# output_module.net
KiCad netlist of a schematic drawn in Altium Designer
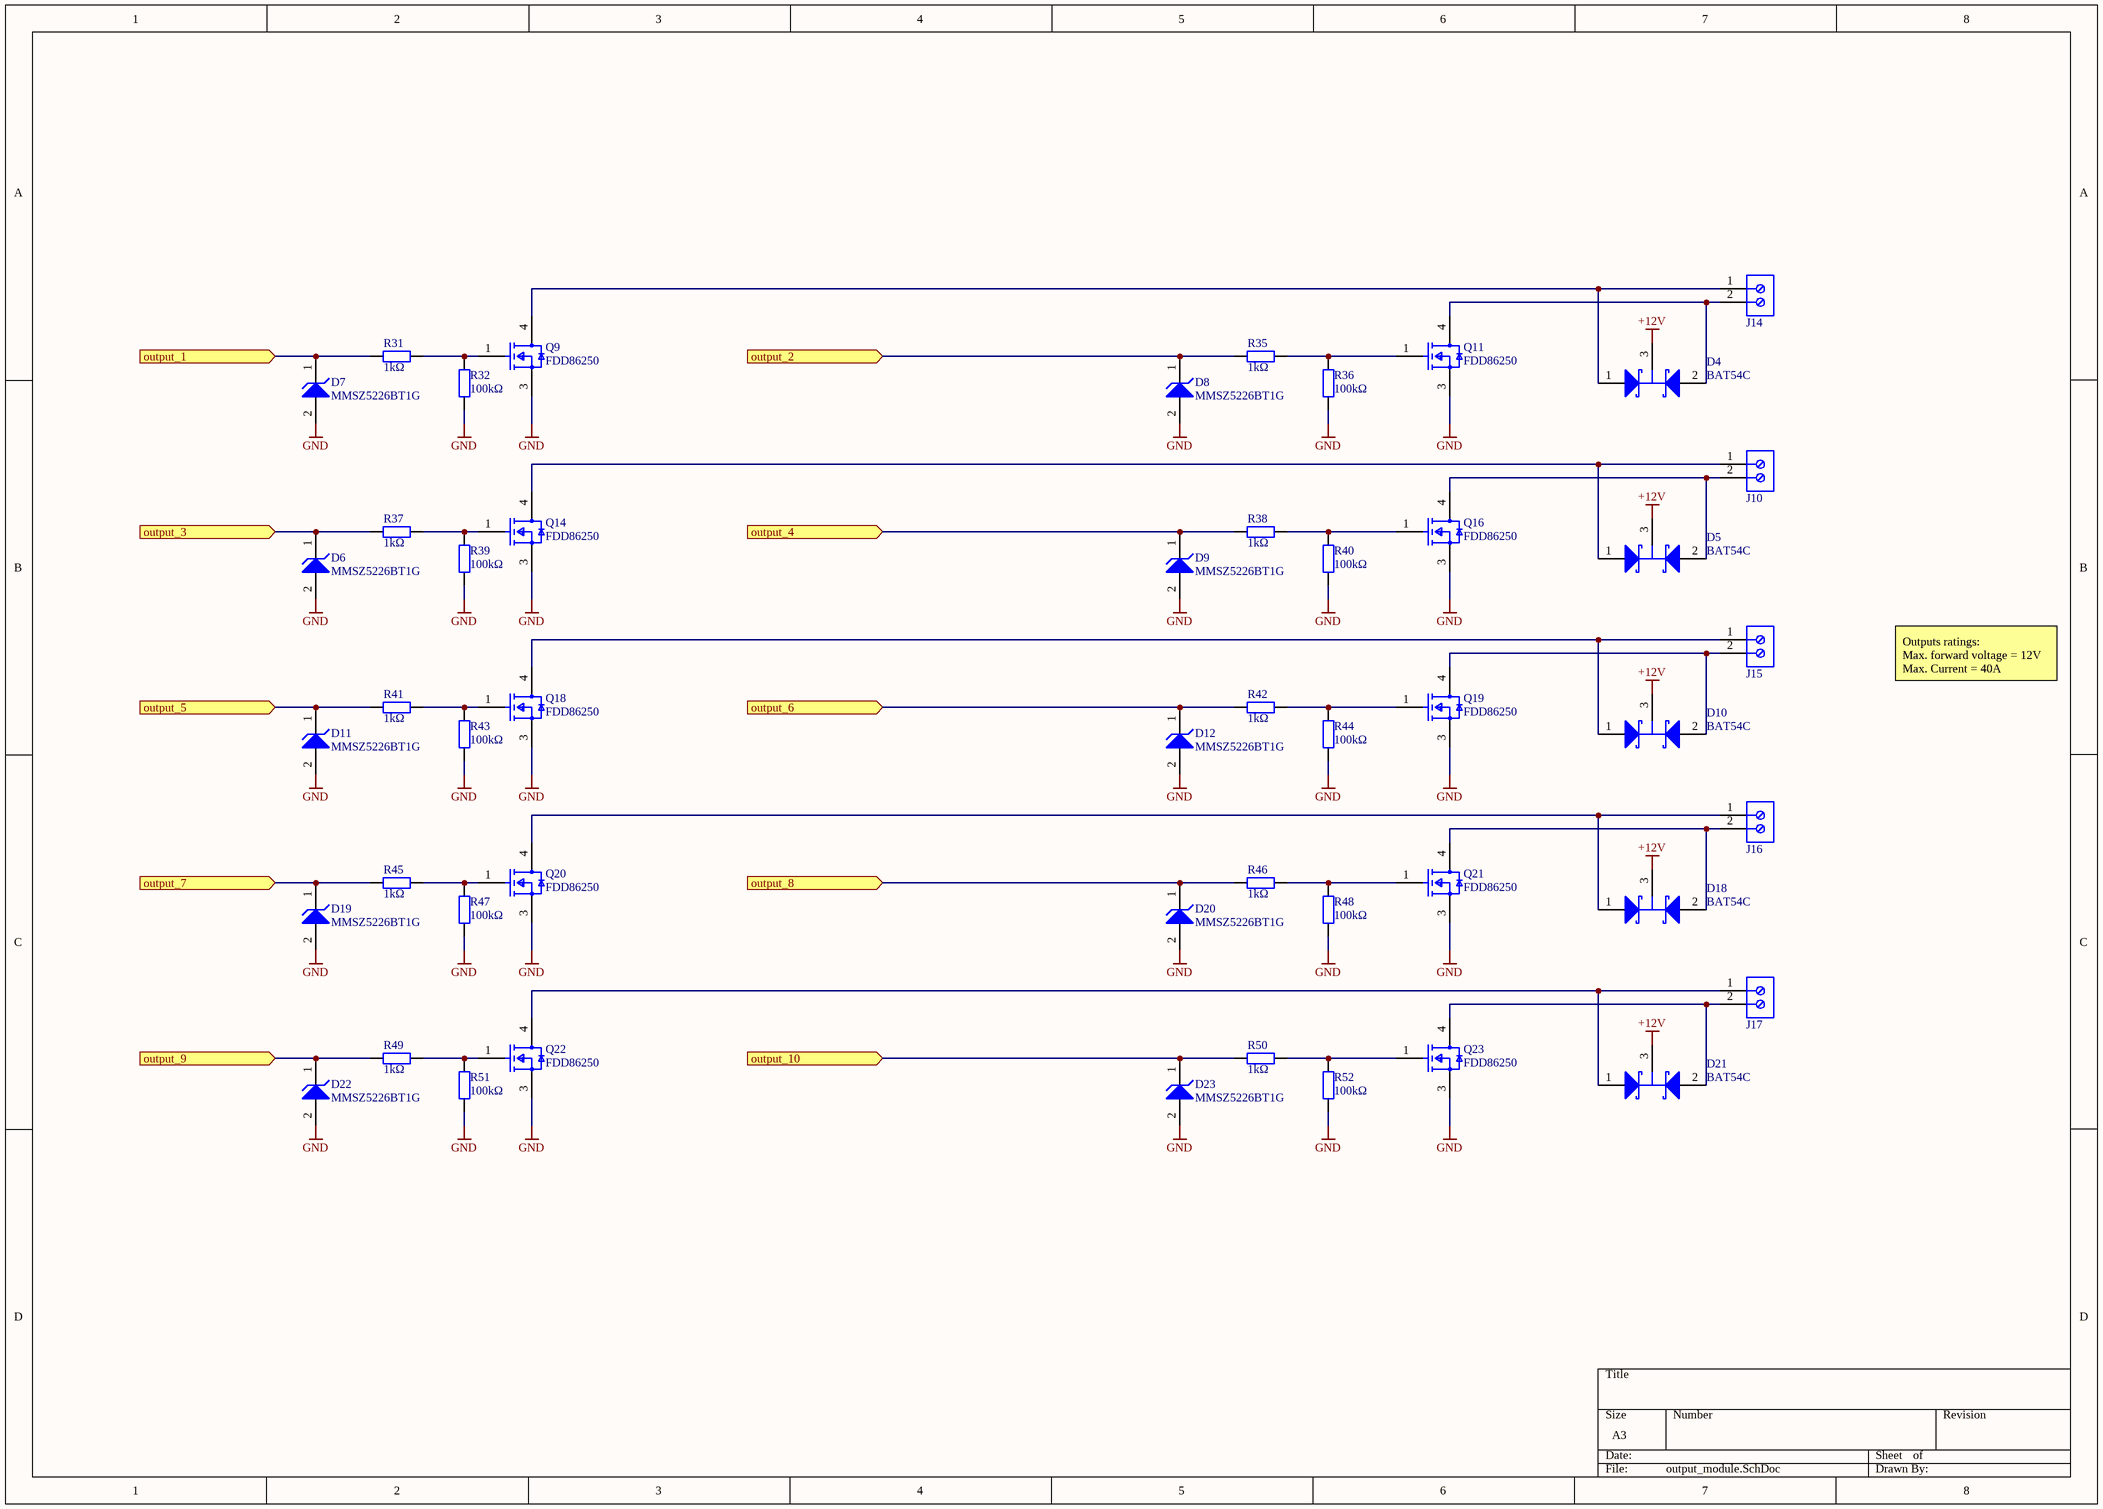
[diagram p0: output_module.SchDoc]

(export (version "E")
  (design (tool "Eeschema 10.0.6"))
  (components
    (comp (ref "D4")
      (value "BAT54C")
      (footprint "SOT-23")
      (description "Schottky Barrier Diode, 30 V, 3-Pin SOT23, RoHS, Tape and Reel")
      (fields (field (name "MANUFACTURER") "NXP Semiconductors"))
      (libsource (lib "integrated_library") (part "DIODE_BAT54C"))
    )
    (comp (ref "D5")
      (value "BAT54C")
      (footprint "SOT-23")
      (description "Schottky Barrier Diode, 30 V, 3-Pin SOT23, RoHS, Tape and Reel")
      (fields (field (name "MANUFACTURER") "NXP Semiconductors"))
      (libsource (lib "integrated_library") (part "DIODE_BAT54C"))
    )
    (comp (ref "D6")
      (value "MMSZ5226BT1G")
      (footprint "ONSC-SOD-123-2-425-04_V")
      (description "Zener Voltage Regulator, 500 mW, 2-Pin SOD-123, Pb-Free, Tape and Reel")
      (fields (field (name "MANUFACTURER") "On Semiconductor"))
      (libsource (lib "Altium Content Vault") (part "ONSC-K1A2-2"))
    )
    (comp (ref "D7")
      (value "MMSZ5226BT1G")
      (footprint "ONSC-SOD-123-2-425-04_V")
      (description "Zener Voltage Regulator, 500 mW, 2-Pin SOD-123, Pb-Free, Tape and Reel")
      (fields (field (name "MANUFACTURER") "On Semiconductor"))
      (libsource (lib "Altium Content Vault") (part "ONSC-K1A2-2"))
    )
    (comp (ref "D8")
      (value "MMSZ5226BT1G")
      (footprint "ONSC-SOD-123-2-425-04_V")
      (description "Zener Voltage Regulator, 500 mW, 2-Pin SOD-123, Pb-Free, Tape and Reel")
      (fields (field (name "MANUFACTURER") "On Semiconductor"))
      (libsource (lib "Altium Content Vault") (part "ONSC-K1A2-2"))
    )
    (comp (ref "D9")
      (value "MMSZ5226BT1G")
      (footprint "ONSC-SOD-123-2-425-04_V")
      (description "Zener Voltage Regulator, 500 mW, 2-Pin SOD-123, Pb-Free, Tape and Reel")
      (fields (field (name "MANUFACTURER") "On Semiconductor"))
      (libsource (lib "Altium Content Vault") (part "ONSC-K1A2-2"))
    )
    (comp (ref "D10")
      (value "BAT54C")
      (footprint "SOT-23")
      (description "Schottky Barrier Diode, 30 V, 3-Pin SOT23, RoHS, Tape and Reel")
      (fields (field (name "MANUFACTURER") "NXP Semiconductors"))
      (libsource (lib "integrated_library") (part "DIODE_BAT54C"))
    )
    (comp (ref "D11")
      (value "MMSZ5226BT1G")
      (footprint "ONSC-SOD-123-2-425-04_V")
      (description "Zener Voltage Regulator, 500 mW, 2-Pin SOD-123, Pb-Free, Tape and Reel")
      (fields (field (name "MANUFACTURER") "On Semiconductor"))
      (libsource (lib "Altium Content Vault") (part "ONSC-K1A2-2"))
    )
    (comp (ref "D12")
      (value "MMSZ5226BT1G")
      (footprint "ONSC-SOD-123-2-425-04_V")
      (description "Zener Voltage Regulator, 500 mW, 2-Pin SOD-123, Pb-Free, Tape and Reel")
      (fields (field (name "MANUFACTURER") "On Semiconductor"))
      (libsource (lib "Altium Content Vault") (part "ONSC-K1A2-2"))
    )
    (comp (ref "D18")
      (value "BAT54C")
      (footprint "SOT-23")
      (description "Schottky Barrier Diode, 30 V, 3-Pin SOT23, RoHS, Tape and Reel")
      (fields (field (name "MANUFACTURER") "NXP Semiconductors"))
      (libsource (lib "integrated_library") (part "DIODE_BAT54C"))
    )
    (comp (ref "D19")
      (value "MMSZ5226BT1G")
      (footprint "ONSC-SOD-123-2-425-04_V")
      (description "Zener Voltage Regulator, 500 mW, 2-Pin SOD-123, Pb-Free, Tape and Reel")
      (fields (field (name "MANUFACTURER") "On Semiconductor"))
      (libsource (lib "Altium Content Vault") (part "ONSC-K1A2-2"))
    )
    (comp (ref "D20")
      (value "MMSZ5226BT1G")
      (footprint "ONSC-SOD-123-2-425-04_V")
      (description "Zener Voltage Regulator, 500 mW, 2-Pin SOD-123, Pb-Free, Tape and Reel")
      (fields (field (name "MANUFACTURER") "On Semiconductor"))
      (libsource (lib "Altium Content Vault") (part "ONSC-K1A2-2"))
    )
    (comp (ref "D21")
      (value "BAT54C")
      (footprint "SOT-23")
      (description "Schottky Barrier Diode, 30 V, 3-Pin SOT23, RoHS, Tape and Reel")
      (fields (field (name "MANUFACTURER") "NXP Semiconductors"))
      (libsource (lib "integrated_library") (part "DIODE_BAT54C"))
    )
    (comp (ref "D22")
      (value "MMSZ5226BT1G")
      (footprint "ONSC-SOD-123-2-425-04_V")
      (description "Zener Voltage Regulator, 500 mW, 2-Pin SOD-123, Pb-Free, Tape and Reel")
      (fields (field (name "MANUFACTURER") "On Semiconductor"))
      (libsource (lib "Altium Content Vault") (part "ONSC-K1A2-2"))
    )
    (comp (ref "D23")
      (value "MMSZ5226BT1G")
      (footprint "ONSC-SOD-123-2-425-04_V")
      (description "Zener Voltage Regulator, 500 mW, 2-Pin SOD-123, Pb-Free, Tape and Reel")
      (fields (field (name "MANUFACTURER") "On Semiconductor"))
      (libsource (lib "Altium Content Vault") (part "ONSC-K1A2-2"))
    )
    (comp (ref "J10")
      (value "282836-2")
      (footprint "TECO-282836-2_V")
      (description "Female Header, Pitch 5 mm, 1 x 2 Position, Height 10 mm, Tail Length 3.5 mm, Rohs, Bulk")
      (fields (field (name "VOLTAGE") "300V") (field (name "MANUFACTURER") "TE Connectivity"))
      (libsource (lib "Altium Content Vault") (part "CN-1P-F-TB2"))
    )
    (comp (ref "J14")
      (value "282836-2")
      (footprint "TECO-282836-2_V")
      (description "Female Header, Pitch 5 mm, 1 x 2 Position, Height 10 mm, Tail Length 3.5 mm, Rohs, Bulk")
      (fields (field (name "VOLTAGE") "300V") (field (name "MANUFACTURER") "TE Connectivity"))
      (libsource (lib "Altium Content Vault") (part "CN-1P-F-TB2"))
    )
    (comp (ref "J15")
      (value "282836-2")
      (footprint "TECO-282836-2_V")
      (description "Female Header, Pitch 5 mm, 1 x 2 Position, Height 10 mm, Tail Length 3.5 mm, Rohs, Bulk")
      (fields (field (name "VOLTAGE") "300V") (field (name "MANUFACTURER") "TE Connectivity"))
      (libsource (lib "Altium Content Vault") (part "CN-1P-F-TB2"))
    )
    (comp (ref "J16")
      (value "282836-2")
      (footprint "TECO-282836-2_V")
      (description "Female Header, Pitch 5 mm, 1 x 2 Position, Height 10 mm, Tail Length 3.5 mm, Rohs, Bulk")
      (fields (field (name "VOLTAGE") "300V") (field (name "MANUFACTURER") "TE Connectivity"))
      (libsource (lib "Altium Content Vault") (part "CN-1P-F-TB2"))
    )
    (comp (ref "J17")
      (value "282836-2")
      (footprint "TECO-282836-2_V")
      (description "Female Header, Pitch 5 mm, 1 x 2 Position, Height 10 mm, Tail Length 3.5 mm, Rohs, Bulk")
      (fields (field (name "VOLTAGE") "300V") (field (name "MANUFACTURER") "TE Connectivity"))
      (libsource (lib "Altium Content Vault") (part "CN-1P-F-TB2"))
    )
    (comp (ref "Q9")
      (value "FDD86250")
      (footprint "FP-369AS-MFG")
      (description "MOSFET N-CH 150V 8A DPAK")
      (fields
        (field (name "MANUFACTURER") "ON Semiconductor")
        (field (name "OCTOPART") "https://octopart.com/fdd86250-on+semiconductor-84325855")
      )
      (libsource (lib "Altium Content Vault") (part "7ccf16d7e298eaa7d64fcf34af6bb8b"))
    )
    (comp (ref "Q11")
      (value "FDD86250")
      (footprint "FP-369AS-MFG")
      (description "MOSFET N-CH 150V 8A DPAK")
      (fields
        (field (name "MANUFACTURER") "ON Semiconductor")
        (field (name "OCTOPART") "https://octopart.com/fdd86250-on+semiconductor-84325855")
      )
      (libsource (lib "Altium Content Vault") (part "7ccf16d7e298eaa7d64fcf34af6bb8b"))
    )
    (comp (ref "Q14")
      (value "FDD86250")
      (footprint "FP-369AS-MFG")
      (description "MOSFET N-CH 150V 8A DPAK")
      (fields
        (field (name "MANUFACTURER") "ON Semiconductor")
        (field (name "OCTOPART") "https://octopart.com/fdd86250-on+semiconductor-84325855")
      )
      (libsource (lib "Altium Content Vault") (part "7ccf16d7e298eaa7d64fcf34af6bb8b"))
    )
    (comp (ref "Q16")
      (value "FDD86250")
      (footprint "FP-369AS-MFG")
      (description "MOSFET N-CH 150V 8A DPAK")
      (fields
        (field (name "MANUFACTURER") "ON Semiconductor")
        (field (name "OCTOPART") "https://octopart.com/fdd86250-on+semiconductor-84325855")
      )
      (libsource (lib "Altium Content Vault") (part "7ccf16d7e298eaa7d64fcf34af6bb8b"))
    )
    (comp (ref "Q18")
      (value "FDD86250")
      (footprint "FP-369AS-MFG")
      (description "MOSFET N-CH 150V 8A DPAK")
      (fields
        (field (name "MANUFACTURER") "ON Semiconductor")
        (field (name "OCTOPART") "https://octopart.com/fdd86250-on+semiconductor-84325855")
      )
      (libsource (lib "Altium Content Vault") (part "7ccf16d7e298eaa7d64fcf34af6bb8b"))
    )
    (comp (ref "Q19")
      (value "FDD86250")
      (footprint "FP-369AS-MFG")
      (description "MOSFET N-CH 150V 8A DPAK")
      (fields
        (field (name "MANUFACTURER") "ON Semiconductor")
        (field (name "OCTOPART") "https://octopart.com/fdd86250-on+semiconductor-84325855")
      )
      (libsource (lib "Altium Content Vault") (part "7ccf16d7e298eaa7d64fcf34af6bb8b"))
    )
    (comp (ref "Q20")
      (value "FDD86250")
      (footprint "FP-369AS-MFG")
      (description "MOSFET N-CH 150V 8A DPAK")
      (fields
        (field (name "MANUFACTURER") "ON Semiconductor")
        (field (name "OCTOPART") "https://octopart.com/fdd86250-on+semiconductor-84325855")
      )
      (libsource (lib "Altium Content Vault") (part "7ccf16d7e298eaa7d64fcf34af6bb8b"))
    )
    (comp (ref "Q21")
      (value "FDD86250")
      (footprint "FP-369AS-MFG")
      (description "MOSFET N-CH 150V 8A DPAK")
      (fields
        (field (name "MANUFACTURER") "ON Semiconductor")
        (field (name "OCTOPART") "https://octopart.com/fdd86250-on+semiconductor-84325855")
      )
      (libsource (lib "Altium Content Vault") (part "7ccf16d7e298eaa7d64fcf34af6bb8b"))
    )
    (comp (ref "Q22")
      (value "FDD86250")
      (footprint "FP-369AS-MFG")
      (description "MOSFET N-CH 150V 8A DPAK")
      (fields
        (field (name "MANUFACTURER") "ON Semiconductor")
        (field (name "OCTOPART") "https://octopart.com/fdd86250-on+semiconductor-84325855")
      )
      (libsource (lib "Altium Content Vault") (part "7ccf16d7e298eaa7d64fcf34af6bb8b"))
    )
    (comp (ref "Q23")
      (value "FDD86250")
      (footprint "FP-369AS-MFG")
      (description "MOSFET N-CH 150V 8A DPAK")
      (fields
        (field (name "MANUFACTURER") "ON Semiconductor")
        (field (name "OCTOPART") "https://octopart.com/fdd86250-on+semiconductor-84325855")
      )
      (libsource (lib "Altium Content Vault") (part "7ccf16d7e298eaa7d64fcf34af6bb8b"))
    )
    (comp (ref "R31")
      (value "1kΩ")
      (footprint "RESC2013X50X30ML20T20")
      (description "Resistor")
      (libsource (lib "PCB_Project") (part "Res_0805"))
    )
    (comp (ref "R32")
      (value "100kΩ")
      (footprint "RESC2013X50X30ML20T20")
      (description "Resistor")
      (libsource (lib "") (part "Res_0805_1"))
    )
    (comp (ref "R35")
      (value "1kΩ")
      (footprint "RESC2013X50X30ML20T20")
      (description "Resistor")
      (libsource (lib "PCB_Project") (part "Res_0805"))
    )
    (comp (ref "R36")
      (value "100kΩ")
      (footprint "RESC2013X50X30ML20T20")
      (description "Resistor")
      (libsource (lib "") (part "Res_0805_1"))
    )
    (comp (ref "R37")
      (value "1kΩ")
      (footprint "RESC2013X50X30ML20T20")
      (description "Resistor")
      (libsource (lib "PCB_Project") (part "Res_0805"))
    )
    (comp (ref "R38")
      (value "1kΩ")
      (footprint "RESC2013X50X30ML20T20")
      (description "Resistor")
      (libsource (lib "PCB_Project") (part "Res_0805"))
    )
    (comp (ref "R39")
      (value "100kΩ")
      (footprint "RESC2013X50X30ML20T20")
      (description "Resistor")
      (libsource (lib "") (part "Res_0805_1"))
    )
    (comp (ref "R40")
      (value "100kΩ")
      (footprint "RESC2013X50X30ML20T20")
      (description "Resistor")
      (libsource (lib "") (part "Res_0805_1"))
    )
    (comp (ref "R41")
      (value "1kΩ")
      (footprint "RESC2013X50X30ML20T20")
      (description "Resistor")
      (libsource (lib "PCB_Project") (part "Res_0805"))
    )
    (comp (ref "R42")
      (value "1kΩ")
      (footprint "RESC2013X50X30ML20T20")
      (description "Resistor")
      (libsource (lib "PCB_Project") (part "Res_0805"))
    )
    (comp (ref "R43")
      (value "100kΩ")
      (footprint "RESC2013X50X30ML20T20")
      (description "Resistor")
      (libsource (lib "") (part "Res_0805_1"))
    )
    (comp (ref "R44")
      (value "100kΩ")
      (footprint "RESC2013X50X30ML20T20")
      (description "Resistor")
      (libsource (lib "") (part "Res_0805_1"))
    )
    (comp (ref "R45")
      (value "1kΩ")
      (footprint "RESC2013X50X30ML20T20")
      (description "Resistor")
      (libsource (lib "PCB_Project") (part "Res_0805"))
    )
    (comp (ref "R46")
      (value "1kΩ")
      (footprint "RESC2013X50X30ML20T20")
      (description "Resistor")
      (libsource (lib "PCB_Project") (part "Res_0805"))
    )
    (comp (ref "R47")
      (value "100kΩ")
      (footprint "RESC2013X50X30ML20T20")
      (description "Resistor")
      (libsource (lib "") (part "Res_0805_1"))
    )
    (comp (ref "R48")
      (value "100kΩ")
      (footprint "RESC2013X50X30ML20T20")
      (description "Resistor")
      (libsource (lib "") (part "Res_0805_1"))
    )
    (comp (ref "R49")
      (value "1kΩ")
      (footprint "RESC2013X50X30ML20T20")
      (description "Resistor")
      (libsource (lib "PCB_Project") (part "Res_0805"))
    )
    (comp (ref "R50")
      (value "1kΩ")
      (footprint "RESC2013X50X30ML20T20")
      (description "Resistor")
      (libsource (lib "PCB_Project") (part "Res_0805"))
    )
    (comp (ref "R51")
      (value "100kΩ")
      (footprint "RESC2013X50X30ML20T20")
      (description "Resistor")
      (libsource (lib "") (part "Res_0805_1"))
    )
    (comp (ref "R52")
      (value "100kΩ")
      (footprint "RESC2013X50X30ML20T20")
      (description "Resistor")
      (libsource (lib "") (part "Res_0805_1"))
    )
  )
  (nets
    (net (code "1") (name "+12V") (class "Default")
      (node (ref "D10") (pin "3") (pinfunction "K_3") (pintype "passive"))
      (node (ref "D18") (pin "3") (pinfunction "K_3") (pintype "passive"))
      (node (ref "D21") (pin "3") (pinfunction "K_3") (pintype "passive"))
      (node (ref "D4") (pin "3") (pinfunction "K_3") (pintype "passive"))
      (node (ref "D5") (pin "3") (pinfunction "K_3") (pintype "passive"))
    )
    (net (code "2") (name "/output_1") (class "Default")
      (node (ref "D7") (pin "1") (pinfunction "K_1") (pintype "passive"))
      (node (ref "R31") (pin "1") (pinfunction "1_1") (pintype "passive"))
    )
    (net (code "3") (name "/output_2") (class "Default")
      (node (ref "D8") (pin "1") (pinfunction "K_1") (pintype "passive"))
      (node (ref "R35") (pin "1") (pinfunction "1_1") (pintype "passive"))
    )
    (net (code "4") (name "/output_3") (class "Default")
      (node (ref "D6") (pin "1") (pinfunction "K_1") (pintype "passive"))
      (node (ref "R37") (pin "1") (pinfunction "1_1") (pintype "passive"))
    )
    (net (code "5") (name "/output_4") (class "Default")
      (node (ref "D9") (pin "1") (pinfunction "K_1") (pintype "passive"))
      (node (ref "R38") (pin "1") (pinfunction "1_1") (pintype "passive"))
    )
    (net (code "6") (name "/output_5") (class "Default")
      (node (ref "D11") (pin "1") (pinfunction "K_1") (pintype "passive"))
      (node (ref "R41") (pin "1") (pinfunction "1_1") (pintype "passive"))
    )
    (net (code "7") (name "/output_6") (class "Default")
      (node (ref "D12") (pin "1") (pinfunction "K_1") (pintype "passive"))
      (node (ref "R42") (pin "1") (pinfunction "1_1") (pintype "passive"))
    )
    (net (code "8") (name "/output_7") (class "Default")
      (node (ref "D19") (pin "1") (pinfunction "K_1") (pintype "passive"))
      (node (ref "R45") (pin "1") (pinfunction "1_1") (pintype "passive"))
    )
    (net (code "9") (name "/output_8") (class "Default")
      (node (ref "D20") (pin "1") (pinfunction "K_1") (pintype "passive"))
      (node (ref "R46") (pin "1") (pinfunction "1_1") (pintype "passive"))
    )
    (net (code "10") (name "/output_9") (class "Default")
      (node (ref "D22") (pin "1") (pinfunction "K_1") (pintype "passive"))
      (node (ref "R49") (pin "1") (pinfunction "1_1") (pintype "passive"))
    )
    (net (code "11") (name "/output_10") (class "Default")
      (node (ref "D23") (pin "1") (pinfunction "K_1") (pintype "passive"))
      (node (ref "R50") (pin "1") (pinfunction "1_1") (pintype "passive"))
    )
    (net (code "12") (name "GND") (class "Default")
      (node (ref "D11") (pin "2") (pinfunction "A_2") (pintype "passive"))
      (node (ref "D12") (pin "2") (pinfunction "A_2") (pintype "passive"))
      (node (ref "D19") (pin "2") (pinfunction "A_2") (pintype "passive"))
      (node (ref "D20") (pin "2") (pinfunction "A_2") (pintype "passive"))
      (node (ref "D22") (pin "2") (pinfunction "A_2") (pintype "passive"))
      (node (ref "D23") (pin "2") (pinfunction "A_2") (pintype "passive"))
      (node (ref "D6") (pin "2") (pinfunction "A_2") (pintype "passive"))
      (node (ref "D7") (pin "2") (pinfunction "A_2") (pintype "passive"))
      (node (ref "D8") (pin "2") (pinfunction "A_2") (pintype "passive"))
      (node (ref "D9") (pin "2") (pinfunction "A_2") (pintype "passive"))
      (node (ref "Q11") (pin "3") (pinfunction "S_3") (pintype "passive"))
      (node (ref "Q14") (pin "3") (pinfunction "S_3") (pintype "passive"))
      (node (ref "Q16") (pin "3") (pinfunction "S_3") (pintype "passive"))
      (node (ref "Q18") (pin "3") (pinfunction "S_3") (pintype "passive"))
      (node (ref "Q19") (pin "3") (pinfunction "S_3") (pintype "passive"))
      (node (ref "Q20") (pin "3") (pinfunction "S_3") (pintype "passive"))
      (node (ref "Q21") (pin "3") (pinfunction "S_3") (pintype "passive"))
      (node (ref "Q22") (pin "3") (pinfunction "S_3") (pintype "passive"))
      (node (ref "Q23") (pin "3") (pinfunction "S_3") (pintype "passive"))
      (node (ref "Q9") (pin "3") (pinfunction "S_3") (pintype "passive"))
      (node (ref "R32") (pin "1") (pinfunction "1_1") (pintype "passive"))
      (node (ref "R36") (pin "1") (pinfunction "1_1") (pintype "passive"))
      (node (ref "R39") (pin "1") (pinfunction "1_1") (pintype "passive"))
      (node (ref "R40") (pin "1") (pinfunction "1_1") (pintype "passive"))
      (node (ref "R43") (pin "1") (pinfunction "1_1") (pintype "passive"))
      (node (ref "R44") (pin "1") (pinfunction "1_1") (pintype "passive"))
      (node (ref "R47") (pin "1") (pinfunction "1_1") (pintype "passive"))
      (node (ref "R48") (pin "1") (pinfunction "1_1") (pintype "passive"))
      (node (ref "R51") (pin "1") (pinfunction "1_1") (pintype "passive"))
      (node (ref "R52") (pin "1") (pinfunction "1_1") (pintype "passive"))
    )
    (net (code "13") (name "Net-(Q9-D)") (class "Default")
      (node (ref "D4") (pin "1") (pinfunction "A_1") (pintype "passive"))
      (node (ref "J14") (pin "1") (pinfunction "1_1") (pintype "passive"))
      (node (ref "Q9") (pin "4") (pinfunction "D_4") (pintype "passive"))
    )
    (net (code "14") (name "Net-(Q9-G)") (class "Default")
      (node (ref "Q9") (pin "1") (pinfunction "G_1") (pintype "passive"))
      (node (ref "R31") (pin "2") (pinfunction "2_2") (pintype "passive"))
      (node (ref "R32") (pin "2") (pinfunction "2_2") (pintype "passive"))
    )
    (net (code "15") (name "Net-(Q11-D)") (class "Default")
      (node (ref "D4") (pin "2") (pinfunction "A_2") (pintype "passive"))
      (node (ref "J14") (pin "2") (pinfunction "2_2") (pintype "passive"))
      (node (ref "Q11") (pin "4") (pinfunction "D_4") (pintype "passive"))
    )
    (net (code "16") (name "Net-(Q11-G)") (class "Default")
      (node (ref "Q11") (pin "1") (pinfunction "G_1") (pintype "passive"))
      (node (ref "R35") (pin "2") (pinfunction "2_2") (pintype "passive"))
      (node (ref "R36") (pin "2") (pinfunction "2_2") (pintype "passive"))
    )
    (net (code "17") (name "Net-(Q14-D)") (class "Default")
      (node (ref "D5") (pin "1") (pinfunction "A_1") (pintype "passive"))
      (node (ref "J10") (pin "1") (pinfunction "1_1") (pintype "passive"))
      (node (ref "Q14") (pin "4") (pinfunction "D_4") (pintype "passive"))
    )
    (net (code "18") (name "Net-(Q14-G)") (class "Default")
      (node (ref "Q14") (pin "1") (pinfunction "G_1") (pintype "passive"))
      (node (ref "R37") (pin "2") (pinfunction "2_2") (pintype "passive"))
      (node (ref "R39") (pin "2") (pinfunction "2_2") (pintype "passive"))
    )
    (net (code "19") (name "Net-(Q16-D)") (class "Default")
      (node (ref "D5") (pin "2") (pinfunction "A_2") (pintype "passive"))
      (node (ref "J10") (pin "2") (pinfunction "2_2") (pintype "passive"))
      (node (ref "Q16") (pin "4") (pinfunction "D_4") (pintype "passive"))
    )
    (net (code "20") (name "Net-(Q16-G)") (class "Default")
      (node (ref "Q16") (pin "1") (pinfunction "G_1") (pintype "passive"))
      (node (ref "R38") (pin "2") (pinfunction "2_2") (pintype "passive"))
      (node (ref "R40") (pin "2") (pinfunction "2_2") (pintype "passive"))
    )
    (net (code "21") (name "Net-(Q18-D)") (class "Default")
      (node (ref "D10") (pin "1") (pinfunction "A_1") (pintype "passive"))
      (node (ref "J15") (pin "1") (pinfunction "1_1") (pintype "passive"))
      (node (ref "Q18") (pin "4") (pinfunction "D_4") (pintype "passive"))
    )
    (net (code "22") (name "Net-(Q18-G)") (class "Default")
      (node (ref "Q18") (pin "1") (pinfunction "G_1") (pintype "passive"))
      (node (ref "R41") (pin "2") (pinfunction "2_2") (pintype "passive"))
      (node (ref "R43") (pin "2") (pinfunction "2_2") (pintype "passive"))
    )
    (net (code "23") (name "Net-(Q19-D)") (class "Default")
      (node (ref "D10") (pin "2") (pinfunction "A_2") (pintype "passive"))
      (node (ref "J15") (pin "2") (pinfunction "2_2") (pintype "passive"))
      (node (ref "Q19") (pin "4") (pinfunction "D_4") (pintype "passive"))
    )
    (net (code "24") (name "Net-(Q19-G)") (class "Default")
      (node (ref "Q19") (pin "1") (pinfunction "G_1") (pintype "passive"))
      (node (ref "R42") (pin "2") (pinfunction "2_2") (pintype "passive"))
      (node (ref "R44") (pin "2") (pinfunction "2_2") (pintype "passive"))
    )
    (net (code "25") (name "Net-(Q20-D)") (class "Default")
      (node (ref "D18") (pin "1") (pinfunction "A_1") (pintype "passive"))
      (node (ref "J16") (pin "1") (pinfunction "1_1") (pintype "passive"))
      (node (ref "Q20") (pin "4") (pinfunction "D_4") (pintype "passive"))
    )
    (net (code "26") (name "Net-(Q20-G)") (class "Default")
      (node (ref "Q20") (pin "1") (pinfunction "G_1") (pintype "passive"))
      (node (ref "R45") (pin "2") (pinfunction "2_2") (pintype "passive"))
      (node (ref "R47") (pin "2") (pinfunction "2_2") (pintype "passive"))
    )
    (net (code "27") (name "Net-(Q21-D)") (class "Default")
      (node (ref "D18") (pin "2") (pinfunction "A_2") (pintype "passive"))
      (node (ref "J16") (pin "2") (pinfunction "2_2") (pintype "passive"))
      (node (ref "Q21") (pin "4") (pinfunction "D_4") (pintype "passive"))
    )
    (net (code "28") (name "Net-(Q21-G)") (class "Default")
      (node (ref "Q21") (pin "1") (pinfunction "G_1") (pintype "passive"))
      (node (ref "R46") (pin "2") (pinfunction "2_2") (pintype "passive"))
      (node (ref "R48") (pin "2") (pinfunction "2_2") (pintype "passive"))
    )
    (net (code "29") (name "Net-(Q22-D)") (class "Default")
      (node (ref "D21") (pin "1") (pinfunction "A_1") (pintype "passive"))
      (node (ref "J17") (pin "1") (pinfunction "1_1") (pintype "passive"))
      (node (ref "Q22") (pin "4") (pinfunction "D_4") (pintype "passive"))
    )
    (net (code "30") (name "Net-(Q22-G)") (class "Default")
      (node (ref "Q22") (pin "1") (pinfunction "G_1") (pintype "passive"))
      (node (ref "R49") (pin "2") (pinfunction "2_2") (pintype "passive"))
      (node (ref "R51") (pin "2") (pinfunction "2_2") (pintype "passive"))
    )
    (net (code "31") (name "Net-(Q23-D)") (class "Default")
      (node (ref "D21") (pin "2") (pinfunction "A_2") (pintype "passive"))
      (node (ref "J17") (pin "2") (pinfunction "2_2") (pintype "passive"))
      (node (ref "Q23") (pin "4") (pinfunction "D_4") (pintype "passive"))
    )
    (net (code "32") (name "Net-(Q23-G)") (class "Default")
      (node (ref "Q23") (pin "1") (pinfunction "G_1") (pintype "passive"))
      (node (ref "R50") (pin "2") (pinfunction "2_2") (pintype "passive"))
      (node (ref "R52") (pin "2") (pinfunction "2_2") (pintype "passive"))
    )
  )
)
